# design.net
KiCad netlist of a schematic drawn in Altium Designer
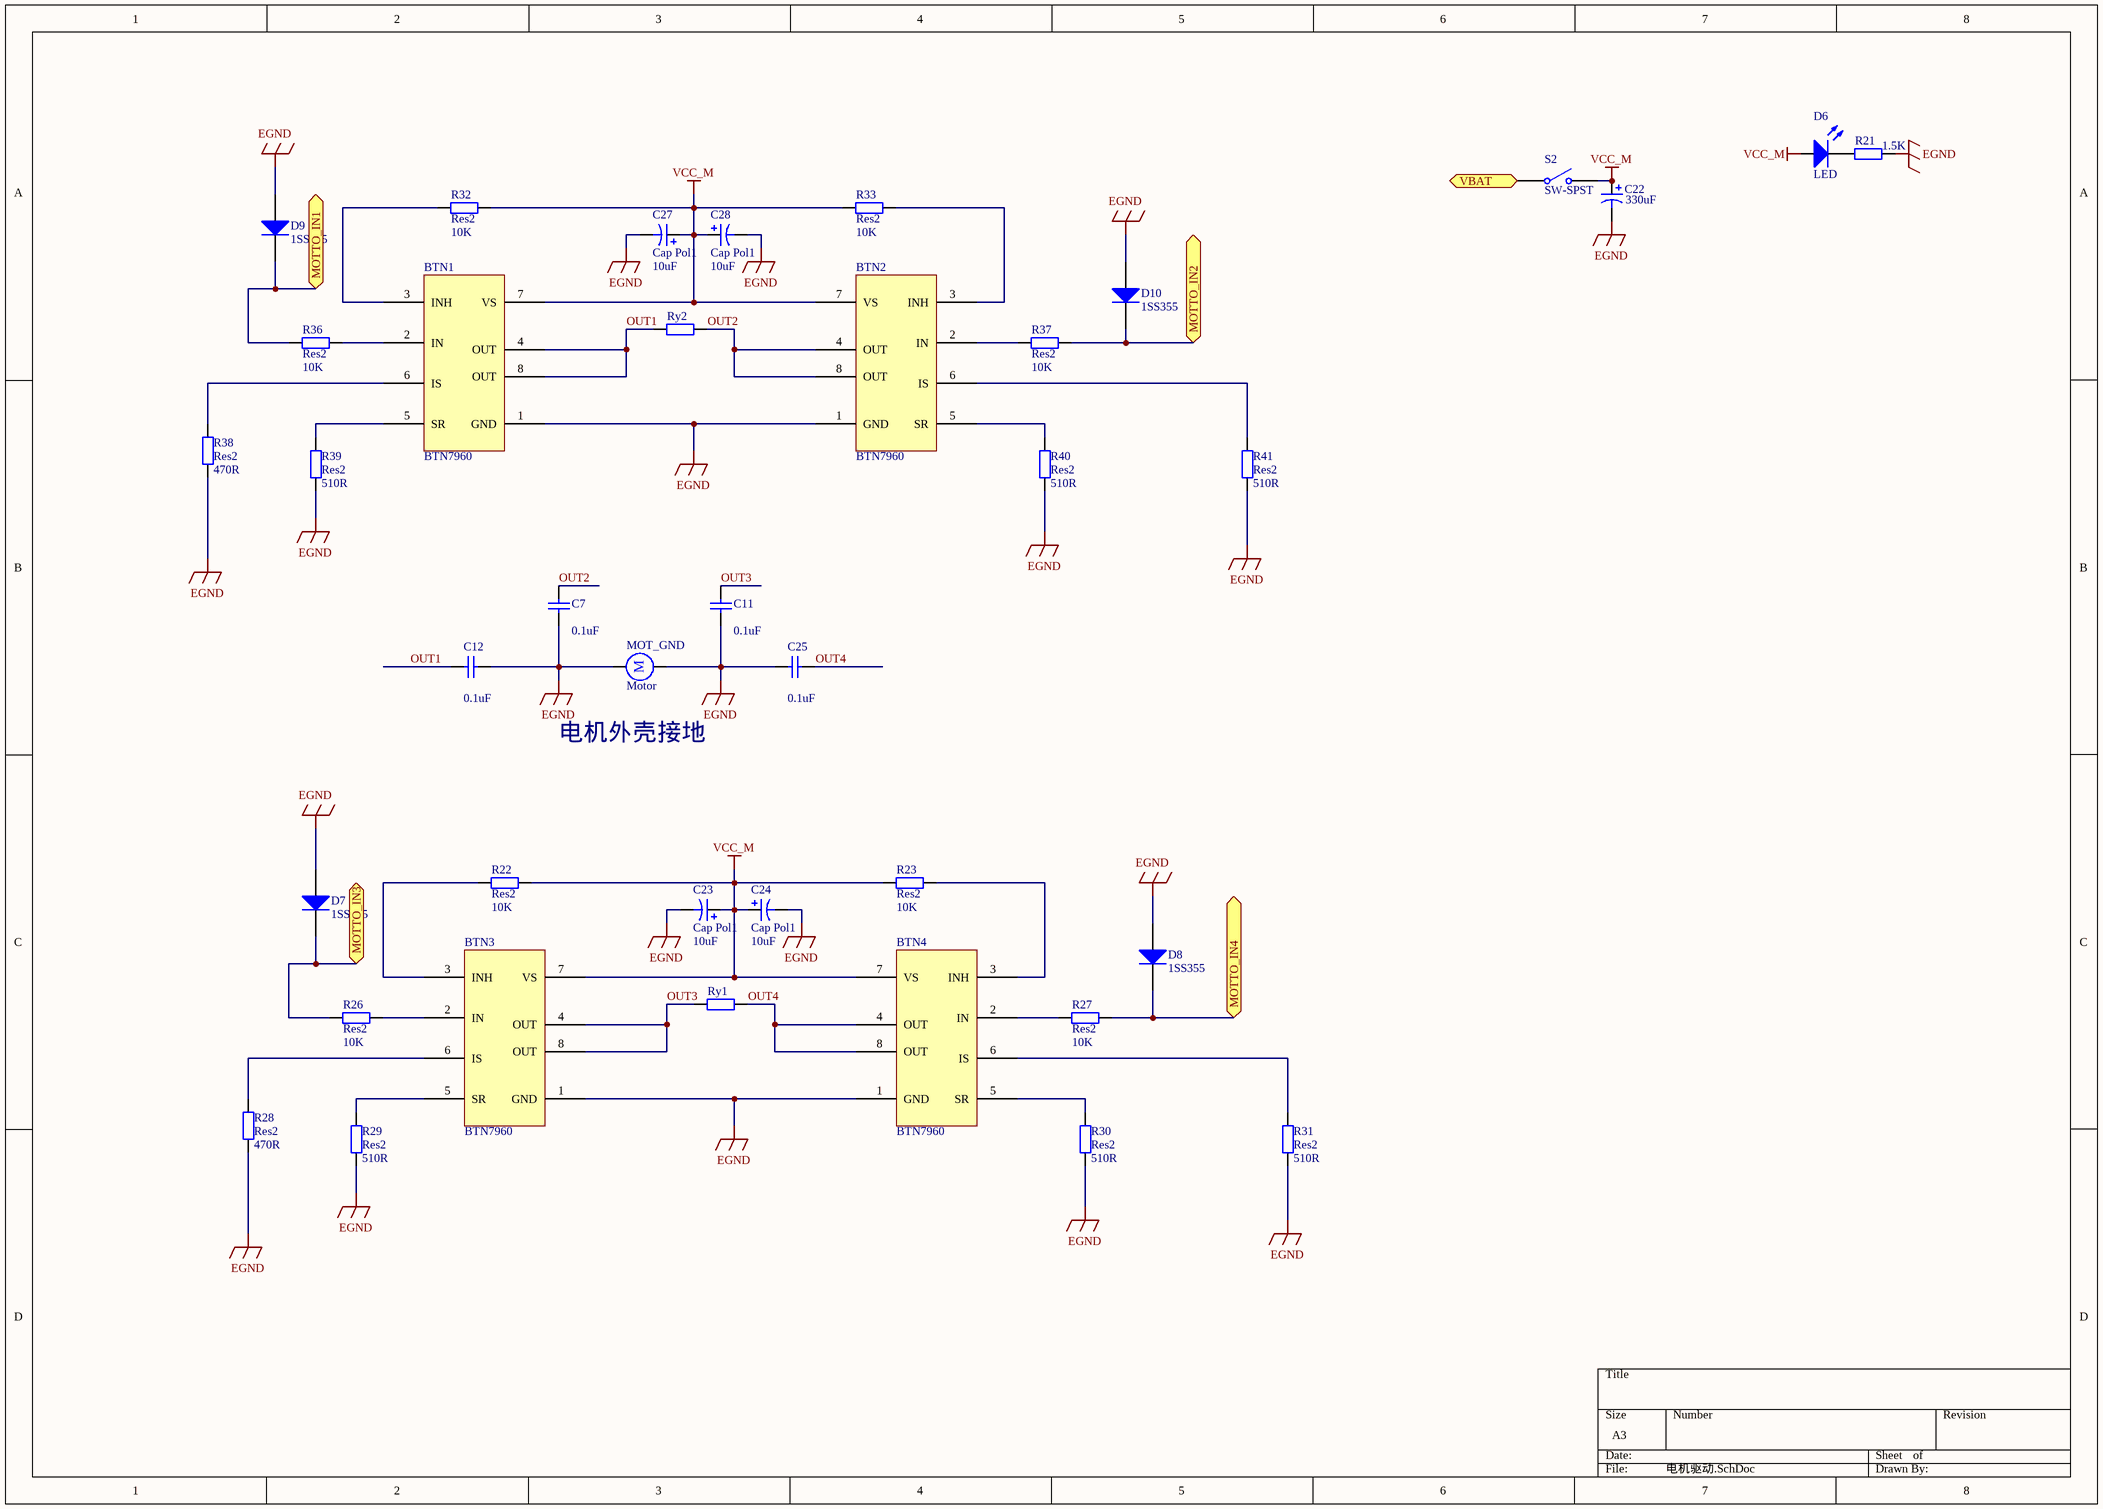
[diagram p0: 电机驱动.SchDoc]

(export (version "E")
  (design (tool "Eeschema 10.0.6"))
  (components
    (comp (ref "BTN1") (value "BTN7960") (footprint "PG-TO263-7-1") (libsource (lib "") (part "BTN7960_1")))
    (comp (ref "BTN2")
      (value "BTN7960")
      (footprint "PG-TO263-7-1")
      (libsource (lib "Landzo") (part "BTN7960"))
    )
    (comp (ref "BTN3") (value "BTN7960") (footprint "PG-TO263-7-1") (libsource (lib "") (part "BTN7960_1")))
    (comp (ref "BTN4")
      (value "BTN7960")
      (footprint "PG-TO263-7-1")
      (libsource (lib "Landzo") (part "BTN7960"))
    )
    (comp (ref "C7")
      (value "0.1uF")
      (footprint "C2012")
      (description "Capacitor")
      (fields (field (name "Comment") "Cap") (field (name "PUBLISHER") "Altium Limited"))
      (libsource (lib "Miscellaneous Devices") (part "Cap"))
    )
    (comp (ref "C11")
      (value "0.1uF")
      (footprint "C2012")
      (description "Capacitor")
      (fields (field (name "Comment") "Cap") (field (name "PUBLISHER") "Altium Limited"))
      (libsource (lib "Miscellaneous Devices") (part "Cap"))
    )
    (comp (ref "C12")
      (value "0.1uF")
      (footprint "C2012")
      (description "Capacitor")
      (fields (field (name "Comment") "Cap") (field (name "PUBLISHER") "Altium Limited"))
      (libsource (lib "Miscellaneous Devices") (part "Cap"))
    )
    (comp (ref "C22")
      (value "330uF")
      (footprint "SMD-EC-F12.5")
      (description "Polarized Capacitor (Radial)")
      (fields (field (name "Comment") "Cap Pol1") (field (name "PUBLISHER") "Altium Limited"))
      (libsource (lib "Miscellaneous Devices") (part "Cap Pol1"))
    )
    (comp (ref "C23")
      (value "Cap Pol1")
      (footprint "1206(2)")
      (description "Polarized Capacitor (Radial)")
      (fields (field (name "ALTIUM_VALUE") "10uF") (field (name "PUBLISHER") "Altium Limited"))
      (libsource (lib "Miscellaneous Devices") (part "Cap Pol1"))
    )
    (comp (ref "C24")
      (value "Cap Pol1")
      (footprint "1206(2)")
      (description "Polarized Capacitor (Radial)")
      (fields (field (name "ALTIUM_VALUE") "10uF") (field (name "PUBLISHER") "Altium Limited"))
      (libsource (lib "Miscellaneous Devices") (part "Cap Pol1"))
    )
    (comp (ref "C25")
      (value "0.1uF")
      (footprint "C2012")
      (description "Capacitor")
      (fields (field (name "Comment") "Cap") (field (name "PUBLISHER") "Altium Limited"))
      (libsource (lib "Miscellaneous Devices") (part "Cap"))
    )
    (comp (ref "C27")
      (value "Cap Pol1")
      (footprint "1206(2)")
      (description "Polarized Capacitor (Radial)")
      (fields (field (name "ALTIUM_VALUE") "10uF") (field (name "PUBLISHER") "Altium Limited"))
      (libsource (lib "Miscellaneous Devices") (part "Cap Pol1"))
    )
    (comp (ref "C28")
      (value "Cap Pol1")
      (footprint "1206(2)")
      (description "Polarized Capacitor (Radial)")
      (fields (field (name "ALTIUM_VALUE") "10uF") (field (name "PUBLISHER") "Altium Limited"))
      (libsource (lib "Miscellaneous Devices") (part "Cap Pol1"))
    )
    (comp (ref "D6")
      (value "LED")
      (footprint "C2012")
      (description "Typical INFRARED GaAs LED")
      (libsource (lib "Landzo") (part "LED"))
    )
    (comp (ref "D7")
      (value "1SS355")
      (footprint "1206(2)")
      (description "High Conductance Fast Diode")
      (fields (field (name "PUBLISHER") "Altium Limited"))
      (libsource (lib "K60-V4.0") (part "Diode 1N4148"))
    )
    (comp (ref "D8")
      (value "1SS355")
      (footprint "1206(2)")
      (description "High Conductance Fast Diode")
      (fields (field (name "PUBLISHER") "Altium Limited"))
      (libsource (lib "K60-V4.0") (part "Diode 1N4148"))
    )
    (comp (ref "D9")
      (value "1SS355")
      (footprint "1206(2)")
      (description "High Conductance Fast Diode")
      (fields (field (name "PUBLISHER") "Altium Limited"))
      (libsource (lib "K60-V4.0") (part "Diode 1N4148"))
    )
    (comp (ref "D10")
      (value "1SS355")
      (footprint "1206(2)")
      (description "High Conductance Fast Diode")
      (fields (field (name "PUBLISHER") "Altium Limited"))
      (libsource (lib "K60-V4.0") (part "Diode 1N4148"))
    )
    (comp (ref "MOT_GND")
      (value "Motor")
      (footprint "KF301-2P")
      (description "Motor, General Kind")
      (libsource (lib "Landzo") (part "Motor"))
    )
    (comp (ref "R21")
      (value "1.5K")
      (footprint "R2012")
      (description "Resistor")
      (fields (field (name "Comment") "Res2") (field (name "PUBLISHER") "Altium Limited"))
      (libsource (lib "") (part "Res2_2"))
    )
    (comp (ref "R22")
      (value "Res2")
      (footprint "R2012")
      (description "Resistor")
      (fields (field (name "ALTIUM_VALUE") "10K") (field (name "PUBLISHER") "Altium Limited"))
      (libsource (lib "Miscellaneous Devices") (part "Res2"))
    )
    (comp (ref "R23")
      (value "Res2")
      (footprint "R2012")
      (description "Resistor")
      (fields (field (name "ALTIUM_VALUE") "10K") (field (name "PUBLISHER") "Altium Limited"))
      (libsource (lib "Miscellaneous Devices") (part "Res2"))
    )
    (comp (ref "R26")
      (value "Res2")
      (footprint "R2012")
      (description "Resistor")
      (fields (field (name "ALTIUM_VALUE") "10K") (field (name "PUBLISHER") "Altium Limited"))
      (libsource (lib "Miscellaneous Devices") (part "Res2"))
    )
    (comp (ref "R27")
      (value "Res2")
      (footprint "R2012")
      (description "Resistor")
      (fields (field (name "ALTIUM_VALUE") "10K") (field (name "PUBLISHER") "Altium Limited"))
      (libsource (lib "Miscellaneous Devices") (part "Res2"))
    )
    (comp (ref "R28")
      (value "Res2")
      (footprint "R2012")
      (description "Resistor")
      (fields (field (name "ALTIUM_VALUE") "470R") (field (name "PUBLISHER") "Altium Limited"))
      (libsource (lib "") (part "Res2_1"))
    )
    (comp (ref "R29")
      (value "Res2")
      (footprint "R2012")
      (description "Resistor")
      (fields (field (name "ALTIUM_VALUE") "510R") (field (name "PUBLISHER") "Altium Limited"))
      (libsource (lib "") (part "Res2_1"))
    )
    (comp (ref "R30")
      (value "Res2")
      (footprint "R2012")
      (description "Resistor")
      (fields (field (name "ALTIUM_VALUE") "510R") (field (name "PUBLISHER") "Altium Limited"))
      (libsource (lib "") (part "Res2_1"))
    )
    (comp (ref "R31")
      (value "Res2")
      (footprint "R2012")
      (description "Resistor")
      (fields (field (name "ALTIUM_VALUE") "510R") (field (name "PUBLISHER") "Altium Limited"))
      (libsource (lib "") (part "Res2_1"))
    )
    (comp (ref "R32")
      (value "Res2")
      (footprint "R2012")
      (description "Resistor")
      (fields (field (name "ALTIUM_VALUE") "10K") (field (name "PUBLISHER") "Altium Limited"))
      (libsource (lib "Miscellaneous Devices") (part "Res2"))
    )
    (comp (ref "R33")
      (value "Res2")
      (footprint "R2012")
      (description "Resistor")
      (fields (field (name "ALTIUM_VALUE") "10K") (field (name "PUBLISHER") "Altium Limited"))
      (libsource (lib "Miscellaneous Devices") (part "Res2"))
    )
    (comp (ref "R36")
      (value "Res2")
      (footprint "R2012")
      (description "Resistor")
      (fields (field (name "ALTIUM_VALUE") "10K") (field (name "PUBLISHER") "Altium Limited"))
      (libsource (lib "Miscellaneous Devices") (part "Res2"))
    )
    (comp (ref "R37")
      (value "Res2")
      (footprint "R2012")
      (description "Resistor")
      (fields (field (name "ALTIUM_VALUE") "10K") (field (name "PUBLISHER") "Altium Limited"))
      (libsource (lib "Miscellaneous Devices") (part "Res2"))
    )
    (comp (ref "R38")
      (value "Res2")
      (footprint "R2012")
      (description "Resistor")
      (fields (field (name "ALTIUM_VALUE") "470R") (field (name "PUBLISHER") "Altium Limited"))
      (libsource (lib "") (part "Res2_1"))
    )
    (comp (ref "R39")
      (value "Res2")
      (footprint "R2012")
      (description "Resistor")
      (fields (field (name "ALTIUM_VALUE") "510R") (field (name "PUBLISHER") "Altium Limited"))
      (libsource (lib "") (part "Res2_1"))
    )
    (comp (ref "R40")
      (value "Res2")
      (footprint "R2012")
      (description "Resistor")
      (fields (field (name "ALTIUM_VALUE") "510R") (field (name "PUBLISHER") "Altium Limited"))
      (libsource (lib "") (part "Res2_1"))
    )
    (comp (ref "R41")
      (value "Res2")
      (footprint "R2012")
      (description "Resistor")
      (fields (field (name "ALTIUM_VALUE") "510R") (field (name "PUBLISHER") "Altium Limited"))
      (libsource (lib "") (part "Res2_1"))
    )
    (comp (ref "Ry1")
      (value "~")
      (footprint "1206(2)")
      (description "Resistor")
      (libsource (lib "Landzo") (part "Res"))
    )
    (comp (ref "Ry2")
      (value "~")
      (footprint "1206(2)")
      (description "Resistor")
      (libsource (lib "Landzo") (part "Res"))
    )
    (comp (ref "S2")
      (value "SW-SPST")
      (footprint "SW-125V6A(-)")
      (description "Single-Pole, Single-Throw Switch")
      (fields (field (name "PUBLISHER") "Altium Limited"))
      (libsource (lib "Miscellaneous Devices") (part "SW-SPST"))
    )
  )
  (nets
    (net (code "1") (name "/MOTTO_IN1") (class "Default")
      (node (ref "D9") (pin "2") (pinfunction "K_2") (pintype "passive"))
      (node (ref "R36") (pin "1") (pinfunction "1_1") (pintype "passive"))
    )
    (net (code "2") (name "/MOTTO_IN2") (class "Default")
      (node (ref "D10") (pin "2") (pinfunction "K_2") (pintype "passive"))
      (node (ref "R37") (pin "2") (pinfunction "2_2") (pintype "passive"))
    )
    (net (code "3") (name "/MOTTO_IN3") (class "Default")
      (node (ref "D7") (pin "2") (pinfunction "K_2") (pintype "passive"))
      (node (ref "R26") (pin "1") (pinfunction "1_1") (pintype "passive"))
    )
    (net (code "4") (name "/MOTTO_IN4") (class "Default")
      (node (ref "D8") (pin "2") (pinfunction "K_2") (pintype "passive"))
      (node (ref "R27") (pin "2") (pinfunction "2_2") (pintype "passive"))
    )
    (net (code "5") (name "/OUT1") (class "Default")
      (node (ref "BTN1") (pin "4") (pinfunction "OUT_4") (pintype "passive"))
      (node (ref "BTN1") (pin "8") (pinfunction "OUT_8") (pintype "passive"))
      (node (ref "C12") (pin "1") (pinfunction "1_1") (pintype "passive"))
      (node (ref "Ry2") (pin "1") (pinfunction "1_1") (pintype "passive"))
    )
    (net (code "6") (name "/OUT2") (class "Default")
      (node (ref "BTN2") (pin "4") (pinfunction "OUT_4") (pintype "passive"))
      (node (ref "BTN2") (pin "8") (pinfunction "OUT_8") (pintype "passive"))
      (node (ref "C7") (pin "1") (pinfunction "1_1") (pintype "passive"))
      (node (ref "Ry2") (pin "2") (pinfunction "2_2") (pintype "passive"))
    )
    (net (code "7") (name "/OUT3") (class "Default")
      (node (ref "BTN3") (pin "4") (pinfunction "OUT_4") (pintype "passive"))
      (node (ref "BTN3") (pin "8") (pinfunction "OUT_8") (pintype "passive"))
      (node (ref "C11") (pin "1") (pinfunction "1_1") (pintype "passive"))
      (node (ref "Ry1") (pin "1") (pinfunction "1_1") (pintype "passive"))
    )
    (net (code "8") (name "/OUT4") (class "Default")
      (node (ref "BTN4") (pin "4") (pinfunction "OUT_4") (pintype "passive"))
      (node (ref "BTN4") (pin "8") (pinfunction "OUT_8") (pintype "passive"))
      (node (ref "C25") (pin "2") (pinfunction "2_2") (pintype "passive"))
      (node (ref "Ry1") (pin "2") (pinfunction "2_2") (pintype "passive"))
    )
    (net (code "9") (name "/VBAT") (class "Default")
      (node (ref "S2") (pin "1") (pinfunction "COMMON_1") (pintype "passive"))
    )
    (net (code "10") (name "EGND") (class "Default")
      (node (ref "BTN1") (pin "1") (pinfunction "GND_1") (pintype "passive"))
      (node (ref "BTN2") (pin "1") (pinfunction "GND_1") (pintype "passive"))
      (node (ref "BTN3") (pin "1") (pinfunction "GND_1") (pintype "passive"))
      (node (ref "BTN4") (pin "1") (pinfunction "GND_1") (pintype "passive"))
      (node (ref "C11") (pin "2") (pinfunction "2_2") (pintype "passive"))
      (node (ref "C12") (pin "2") (pinfunction "2_2") (pintype "passive"))
      (node (ref "C22") (pin "2") (pinfunction "2_2") (pintype "passive"))
      (node (ref "C23") (pin "2") (pinfunction "2_2") (pintype "passive"))
      (node (ref "C24") (pin "2") (pinfunction "2_2") (pintype "passive"))
      (node (ref "C25") (pin "1") (pinfunction "1_1") (pintype "passive"))
      (node (ref "C27") (pin "2") (pinfunction "2_2") (pintype "passive"))
      (node (ref "C28") (pin "2") (pinfunction "2_2") (pintype "passive"))
      (node (ref "C7") (pin "2") (pinfunction "2_2") (pintype "passive"))
      (node (ref "D10") (pin "1") (pinfunction "A_1") (pintype "passive"))
      (node (ref "D7") (pin "1") (pinfunction "A_1") (pintype "passive"))
      (node (ref "D8") (pin "1") (pinfunction "A_1") (pintype "passive"))
      (node (ref "D9") (pin "1") (pinfunction "A_1") (pintype "passive"))
      (node (ref "MOT_GND") (pin "1") (pinfunction "1_1") (pintype "passive"))
      (node (ref "MOT_GND") (pin "2") (pinfunction "2_2") (pintype "passive"))
      (node (ref "R21") (pin "1") (pinfunction "1_1") (pintype "passive"))
      (node (ref "R28") (pin "1") (pinfunction "1_1") (pintype "passive"))
      (node (ref "R29") (pin "1") (pinfunction "1_1") (pintype "passive"))
      (node (ref "R30") (pin "1") (pinfunction "1_1") (pintype "passive"))
      (node (ref "R31") (pin "1") (pinfunction "1_1") (pintype "passive"))
      (node (ref "R38") (pin "1") (pinfunction "1_1") (pintype "passive"))
      (node (ref "R39") (pin "1") (pinfunction "1_1") (pintype "passive"))
      (node (ref "R40") (pin "1") (pinfunction "1_1") (pintype "passive"))
      (node (ref "R41") (pin "1") (pinfunction "1_1") (pintype "passive"))
    )
    (net (code "11") (name "Net-(BTN1-IN)") (class "Default")
      (node (ref "BTN1") (pin "2") (pinfunction "IN_2") (pintype "passive"))
      (node (ref "R36") (pin "2") (pinfunction "2_2") (pintype "passive"))
    )
    (net (code "12") (name "Net-(BTN1-INH)") (class "Default")
      (node (ref "BTN1") (pin "3") (pinfunction "INH_3") (pintype "passive"))
      (node (ref "R32") (pin "1") (pinfunction "1_1") (pintype "passive"))
    )
    (net (code "13") (name "Net-(BTN1-IS)") (class "Default")
      (node (ref "BTN1") (pin "6") (pinfunction "IS_6") (pintype "passive"))
      (node (ref "R38") (pin "2") (pinfunction "2_2") (pintype "passive"))
    )
    (net (code "14") (name "Net-(BTN1-SR)") (class "Default")
      (node (ref "BTN1") (pin "5") (pinfunction "SR_5") (pintype "passive"))
      (node (ref "R39") (pin "2") (pinfunction "2_2") (pintype "passive"))
    )
    (net (code "15") (name "Net-(BTN2-IN)") (class "Default")
      (node (ref "BTN2") (pin "2") (pinfunction "IN_2") (pintype "passive"))
      (node (ref "R37") (pin "1") (pinfunction "1_1") (pintype "passive"))
    )
    (net (code "16") (name "Net-(BTN2-INH)") (class "Default")
      (node (ref "BTN2") (pin "3") (pinfunction "INH_3") (pintype "passive"))
      (node (ref "R33") (pin "2") (pinfunction "2_2") (pintype "passive"))
    )
    (net (code "17") (name "Net-(BTN2-IS)") (class "Default")
      (node (ref "BTN2") (pin "6") (pinfunction "IS_6") (pintype "passive"))
      (node (ref "R41") (pin "2") (pinfunction "2_2") (pintype "passive"))
    )
    (net (code "18") (name "Net-(BTN2-SR)") (class "Default")
      (node (ref "BTN2") (pin "5") (pinfunction "SR_5") (pintype "passive"))
      (node (ref "R40") (pin "2") (pinfunction "2_2") (pintype "passive"))
    )
    (net (code "19") (name "Net-(BTN3-IN)") (class "Default")
      (node (ref "BTN3") (pin "2") (pinfunction "IN_2") (pintype "passive"))
      (node (ref "R26") (pin "2") (pinfunction "2_2") (pintype "passive"))
    )
    (net (code "20") (name "Net-(BTN3-INH)") (class "Default")
      (node (ref "BTN3") (pin "3") (pinfunction "INH_3") (pintype "passive"))
      (node (ref "R22") (pin "1") (pinfunction "1_1") (pintype "passive"))
    )
    (net (code "21") (name "Net-(BTN3-IS)") (class "Default")
      (node (ref "BTN3") (pin "6") (pinfunction "IS_6") (pintype "passive"))
      (node (ref "R28") (pin "2") (pinfunction "2_2") (pintype "passive"))
    )
    (net (code "22") (name "Net-(BTN3-SR)") (class "Default")
      (node (ref "BTN3") (pin "5") (pinfunction "SR_5") (pintype "passive"))
      (node (ref "R29") (pin "2") (pinfunction "2_2") (pintype "passive"))
    )
    (net (code "23") (name "Net-(BTN4-IN)") (class "Default")
      (node (ref "BTN4") (pin "2") (pinfunction "IN_2") (pintype "passive"))
      (node (ref "R27") (pin "1") (pinfunction "1_1") (pintype "passive"))
    )
    (net (code "24") (name "Net-(BTN4-INH)") (class "Default")
      (node (ref "BTN4") (pin "3") (pinfunction "INH_3") (pintype "passive"))
      (node (ref "R23") (pin "2") (pinfunction "2_2") (pintype "passive"))
    )
    (net (code "25") (name "Net-(BTN4-IS)") (class "Default")
      (node (ref "BTN4") (pin "6") (pinfunction "IS_6") (pintype "passive"))
      (node (ref "R31") (pin "2") (pinfunction "2_2") (pintype "passive"))
    )
    (net (code "26") (name "Net-(BTN4-SR)") (class "Default")
      (node (ref "BTN4") (pin "5") (pinfunction "SR_5") (pintype "passive"))
      (node (ref "R30") (pin "2") (pinfunction "2_2") (pintype "passive"))
    )
    (net (code "27") (name "Net-(D6-Pad2)") (class "Default")
      (node (ref "D6") (pin "2") (pinfunction "2_2") (pintype "passive"))
      (node (ref "R21") (pin "2") (pinfunction "2_2") (pintype "passive"))
    )
    (net (code "28") (name "VCC_M") (class "Default")
      (node (ref "BTN1") (pin "7") (pinfunction "VS_7") (pintype "passive"))
      (node (ref "BTN2") (pin "7") (pinfunction "VS_7") (pintype "passive"))
      (node (ref "BTN3") (pin "7") (pinfunction "VS_7") (pintype "passive"))
      (node (ref "BTN4") (pin "7") (pinfunction "VS_7") (pintype "passive"))
      (node (ref "C22") (pin "1") (pinfunction "1_1") (pintype "passive"))
      (node (ref "C23") (pin "1") (pinfunction "1_1") (pintype "passive"))
      (node (ref "C24") (pin "1") (pinfunction "1_1") (pintype "passive"))
      (node (ref "C27") (pin "1") (pinfunction "1_1") (pintype "passive"))
      (node (ref "C28") (pin "1") (pinfunction "1_1") (pintype "passive"))
      (node (ref "D6") (pin "1") (pinfunction "1_1") (pintype "passive"))
      (node (ref "R22") (pin "2") (pinfunction "2_2") (pintype "passive"))
      (node (ref "R23") (pin "1") (pinfunction "1_1") (pintype "passive"))
      (node (ref "R32") (pin "2") (pinfunction "2_2") (pintype "passive"))
      (node (ref "R33") (pin "1") (pinfunction "1_1") (pintype "passive"))
      (node (ref "S2") (pin "2") (pinfunction "NO_2") (pintype "passive"))
    )
  )
)
